# Groupe3_Hermant-Bohyn-Almasy-Ponjee.net
KiCad netlist of a schematic drawn in EAGLE
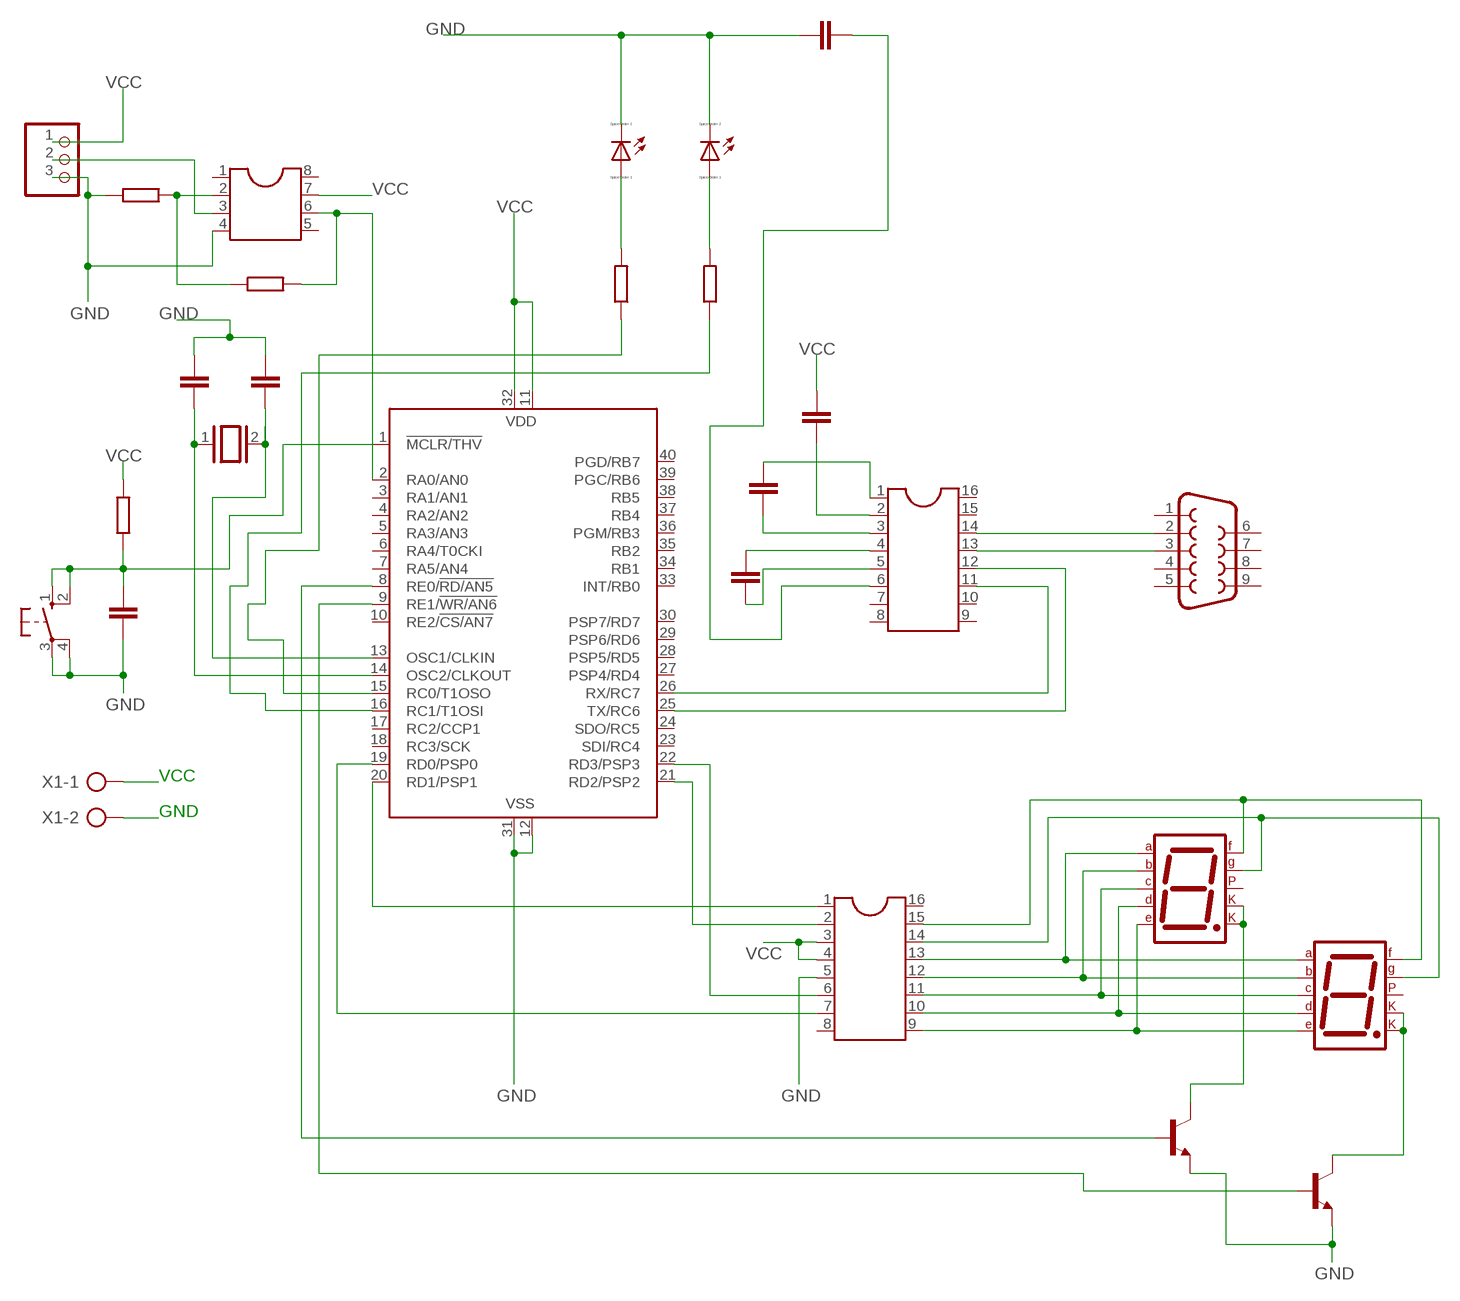
[diagram p0: schematic, sheet 1]

(export (version "E")
  (design (tool "Eeschema 10.0.6"))
  (components
    (comp (ref "4511")
      (value "DIL16")
      (footprint "eagle-import:DIL16")
      (libsource (lib "eagle-import") (part "DIL16"))
    )
    (comp (ref "AMPLIOP")
      (value "DIL8")
      (footprint "eagle-import:DIL08")
      (libsource (lib "eagle-import") (part "DIL8"))
    )
    (comp (ref "C1")
      (value "15pF")
      (footprint "eagle-import:C025-050X050")
      (libsource (lib "eagle-import") (part "C-EU025-050X050"))
    )
    (comp (ref "C2")
      (value "15pF")
      (footprint "eagle-import:C025-050X050")
      (libsource (lib "eagle-import") (part "C-EU025-050X050"))
    )
    (comp (ref "C3")
      (value "1uF")
      (footprint "eagle-import:C025-050X050")
      (libsource (lib "eagle-import") (part "C-EU025-050X050"))
    )
    (comp (ref "C4")
      (value "10uF")
      (footprint "eagle-import:C025-050X050")
      (libsource (lib "eagle-import") (part "C-EU025-050X050"))
    )
    (comp (ref "C5")
      (value "10uF")
      (footprint "eagle-import:C025-050X050")
      (libsource (lib "eagle-import") (part "C-EU025-050X050"))
    )
    (comp (ref "C7")
      (value "10uF")
      (footprint "eagle-import:C025-050X050")
      (libsource (lib "eagle-import") (part "C-EU025-050X050"))
    )
    (comp (ref "C61")
      (value "10uF")
      (footprint "eagle-import:C025-050X050")
      (libsource (lib "eagle-import") (part "C-EU025-050X050"))
    )
    (comp (ref "D1")
      (value "7SEG-CK")
      (footprint "eagle-import:7SEG-13")
      (libsource (lib "eagle-import") (part "7SEG-CK"))
    )
    (comp (ref "D2")
      (value "7SEG-CK")
      (footprint "eagle-import:7SEG-13")
      (libsource (lib "eagle-import") (part "7SEG-CK"))
    )
    (comp (ref "LED1")
      (value "LED_ELD260")
      (footprint "eagle-import:LED_LD260")
      (libsource (lib "eagle-import") (part "LED_ELD260"))
    )
    (comp (ref "LED2")
      (value "LED_ELD260")
      (footprint "eagle-import:LED_LD260")
      (libsource (lib "eagle-import") (part "LED_ELD260"))
    )
    (comp (ref "LM35")
      (value "PINHD-1X3")
      (footprint "eagle-import:1X03")
      (libsource (lib "eagle-import") (part "PINHD-1X3"))
    )
    (comp (ref "MAX232")
      (value "DIL16")
      (footprint "eagle-import:DIL16")
      (libsource (lib "eagle-import") (part "DIL16"))
    )
    (comp (ref "P1/COMPIM")
      (value "F09V")
      (footprint "eagle-import:F09V")
      (libsource (lib "eagle-import") (part "F09V"))
    )
    (comp (ref "Q1")
      (value "2N2222")
      (footprint "eagle-import:TO18")
      (libsource (lib "eagle-import") (part "2N2222"))
    )
    (comp (ref "Q2")
      (value "2N2222")
      (footprint "eagle-import:TO18")
      (libsource (lib "eagle-import") (part "2N2222"))
    )
    (comp (ref "R1")
      (value "10k")
      (footprint "eagle-import:0204_7")
      (libsource (lib "eagle-import") (part "R-EU_0204/7"))
    )
    (comp (ref "R2")
      (value "4k")
      (footprint "eagle-import:0204_7")
      (libsource (lib "eagle-import") (part "R-EU_0204/7"))
    )
    (comp (ref "R3")
      (value "1k")
      (footprint "eagle-import:0204_7")
      (libsource (lib "eagle-import") (part "R-EU_0204/7"))
    )
    (comp (ref "R4")
      (value "280")
      (footprint "eagle-import:0204_7")
      (libsource (lib "eagle-import") (part "R-EU_0204/7"))
    )
    (comp (ref "R5")
      (value "280")
      (footprint "eagle-import:0204_7")
      (libsource (lib "eagle-import") (part "R-EU_0204/7"))
    )
    (comp (ref "S1")
      (value "10-XX")
      (footprint "eagle-import:B3F-10XX")
      (fields (field (name "MPN") "B3F-1000"))
      (libsource (lib "eagle-import") (part "10-XX"))
    )
    (comp (ref "U1")
      (value "PIC16F877P")
      (footprint "eagle-import:DIL40")
      (fields (field (name "MF") "MICROCHIP") (field (name "MPN") "PIC16F877-04/P"))
      (libsource (lib "eagle-import") (part "PIC16F87P7"))
    )
    (comp (ref "X1")
      (value "AK300/2")
      (footprint "eagle-import:AK300_2")
      (libsource (lib "eagle-import") (part "AK300/2"))
    )
    (comp (ref "X11")
      (value "XTAL/S")
      (footprint "eagle-import:QS")
      (libsource (lib "eagle-import") (part "XTAL/S"))
    )
  )
  (nets
    (net (code "1") (name "/GND") (class "Default")
      (node (ref "4511") (pin "5") (pinfunction "5_5") (pintype "passive"))
      (node (ref "AMPLIOP") (pin "4") (pinfunction "4_4") (pintype "passive"))
      (node (ref "C1") (pin "1") (pinfunction "1_1") (pintype "passive"))
      (node (ref "C2") (pin "1") (pinfunction "1_1") (pintype "passive"))
      (node (ref "C3") (pin "1") (pinfunction "1_1") (pintype "passive"))
      (node (ref "C61") (pin "2") (pinfunction "2_2") (pintype "passive"))
      (node (ref "LED1") (pin "K") (pinfunction "C_K") (pintype "passive"))
      (node (ref "LED2") (pin "K") (pinfunction "C_K") (pintype "passive"))
      (node (ref "LM35") (pin "3") (pinfunction "3_3") (pintype "passive"))
      (node (ref "Q1") (pin "1") (pinfunction "E_1") (pintype "passive"))
      (node (ref "Q2") (pin "1") (pinfunction "E_1") (pintype "passive"))
      (node (ref "R2") (pin "1") (pinfunction "1_1") (pintype "passive"))
      (node (ref "S1") (pin "3") (pinfunction "P_3") (pintype "passive"))
      (node (ref "S1") (pin "4") (pinfunction "P1_4") (pintype "passive"))
      (node (ref "U1") (pin "12") (pinfunction "VSS_12") (pintype "power_in"))
      (node (ref "U1") (pin "31") (pinfunction "VSS_31") (pintype "power_in"))
      (node (ref "X1") (pin "2") (pinfunction "KL_2") (pintype "passive"))
    )
    (net (code "2") (name "/VCC") (class "Default")
      (node (ref "4511") (pin "3") (pinfunction "3_3") (pintype "passive"))
      (node (ref "4511") (pin "4") (pinfunction "4_4") (pintype "passive"))
      (node (ref "AMPLIOP") (pin "7") (pinfunction "7_7") (pintype "passive"))
      (node (ref "C7") (pin "2") (pinfunction "2_2") (pintype "passive"))
      (node (ref "LM35") (pin "1") (pinfunction "1_1") (pintype "passive"))
      (node (ref "R1") (pin "2") (pinfunction "2_2") (pintype "passive"))
      (node (ref "U1") (pin "11") (pinfunction "VDD_11") (pintype "power_in"))
      (node (ref "U1") (pin "32") (pinfunction "VDD_32") (pintype "power_in"))
      (node (ref "X1") (pin "1") (pinfunction "KL_1") (pintype "passive"))
    )
    (net (code "3") (name "Net-(AMPLIOP-Pad2)") (class "Default")
      (node (ref "AMPLIOP") (pin "2") (pinfunction "2_2") (pintype "passive"))
      (node (ref "R2") (pin "2") (pinfunction "2_2") (pintype "passive"))
      (node (ref "R3") (pin "1") (pinfunction "1_1") (pintype "passive"))
    )
    (net (code "4") (name "Net-(AMPLIOP-Pad3)") (class "Default")
      (node (ref "AMPLIOP") (pin "3") (pinfunction "3_3") (pintype "passive"))
      (node (ref "LM35") (pin "2") (pinfunction "2_2") (pintype "passive"))
    )
    (net (code "5") (name "Net-(C4-Pad1)") (class "Default")
      (node (ref "C4") (pin "1") (pinfunction "1_1") (pintype "passive"))
      (node (ref "MAX232") (pin "3") (pinfunction "3_3") (pintype "passive"))
    )
    (net (code "6") (name "Net-(C4-Pad2)") (class "Default")
      (node (ref "C4") (pin "2") (pinfunction "2_2") (pintype "passive"))
      (node (ref "MAX232") (pin "1") (pinfunction "1_1") (pintype "passive"))
    )
    (net (code "7") (name "Net-(C5-Pad1)") (class "Default")
      (node (ref "C5") (pin "1") (pinfunction "1_1") (pintype "passive"))
      (node (ref "MAX232") (pin "5") (pinfunction "5_5") (pintype "passive"))
    )
    (net (code "8") (name "Net-(C5-Pad2)") (class "Default")
      (node (ref "C5") (pin "2") (pinfunction "2_2") (pintype "passive"))
      (node (ref "MAX232") (pin "4") (pinfunction "4_4") (pintype "passive"))
    )
    (net (code "9") (name "Net-(C7-Pad1)") (class "Default")
      (node (ref "C7") (pin "1") (pinfunction "1_1") (pintype "passive"))
      (node (ref "MAX232") (pin "2") (pinfunction "2_2") (pintype "passive"))
    )
    (net (code "10") (name "Net-(C61-Pad1)") (class "Default")
      (node (ref "C61") (pin "1") (pinfunction "1_1") (pintype "passive"))
      (node (ref "MAX232") (pin "6") (pinfunction "6_6") (pintype "passive"))
    )
    (net (code "11") (name "Net-(D1-A)") (class "Default")
      (node (ref "4511") (pin "13") (pinfunction "13_13") (pintype "passive"))
      (node (ref "D1") (pin "7") (pinfunction "A_7") (pintype "passive"))
      (node (ref "D2") (pin "7") (pinfunction "A_7") (pintype "passive"))
    )
    (net (code "12") (name "Net-(D1-B)") (class "Default")
      (node (ref "4511") (pin "12") (pinfunction "12_12") (pintype "passive"))
      (node (ref "D1") (pin "6") (pinfunction "B_6") (pintype "passive"))
      (node (ref "D2") (pin "6") (pinfunction "B_6") (pintype "passive"))
    )
    (net (code "13") (name "Net-(D1-C)") (class "Default")
      (node (ref "4511") (pin "11") (pinfunction "11_11") (pintype "passive"))
      (node (ref "D1") (pin "4") (pinfunction "C_4") (pintype "passive"))
      (node (ref "D2") (pin "4") (pinfunction "C_4") (pintype "passive"))
    )
    (net (code "14") (name "Net-(D1-CK1)") (class "Default")
      (node (ref "D1") (pin "3") (pinfunction "CK1_3") (pintype "passive"))
      (node (ref "D1") (pin "8") (pinfunction "CK2_8") (pintype "passive"))
      (node (ref "Q1") (pin "3") (pinfunction "C_3") (pintype "passive"))
    )
    (net (code "15") (name "Net-(D1-D)") (class "Default")
      (node (ref "4511") (pin "10") (pinfunction "10_10") (pintype "passive"))
      (node (ref "D1") (pin "2") (pinfunction "D_2") (pintype "passive"))
      (node (ref "D2") (pin "2") (pinfunction "D_2") (pintype "passive"))
    )
    (net (code "16") (name "Net-(D1-E)") (class "Default")
      (node (ref "4511") (pin "9") (pinfunction "9_9") (pintype "passive"))
      (node (ref "D1") (pin "1") (pinfunction "E_1") (pintype "passive"))
      (node (ref "D2") (pin "1") (pinfunction "E_1") (pintype "passive"))
    )
    (net (code "17") (name "Net-(D1-F)") (class "Default")
      (node (ref "4511") (pin "15") (pinfunction "15_15") (pintype "passive"))
      (node (ref "D1") (pin "9") (pinfunction "F_9") (pintype "passive"))
      (node (ref "D2") (pin "9") (pinfunction "F_9") (pintype "passive"))
    )
    (net (code "18") (name "Net-(D1-G)") (class "Default")
      (node (ref "4511") (pin "14") (pinfunction "14_14") (pintype "passive"))
      (node (ref "D1") (pin "10") (pinfunction "G_10") (pintype "passive"))
      (node (ref "D2") (pin "10") (pinfunction "G_10") (pintype "passive"))
    )
    (net (code "19") (name "Net-(D2-CK1)") (class "Default")
      (node (ref "D2") (pin "3") (pinfunction "CK1_3") (pintype "passive"))
      (node (ref "D2") (pin "8") (pinfunction "CK2_8") (pintype "passive"))
      (node (ref "Q2") (pin "3") (pinfunction "C_3") (pintype "passive"))
    )
    (net (code "20") (name "Net-(LED1-PadA)") (class "Default")
      (node (ref "LED1") (pin "A") (pinfunction "A_A") (pintype "passive"))
      (node (ref "R4") (pin "2") (pinfunction "2_2") (pintype "passive"))
    )
    (net (code "21") (name "Net-(LED2-PadA)") (class "Default")
      (node (ref "LED2") (pin "A") (pinfunction "A_A") (pintype "passive"))
      (node (ref "R5") (pin "2") (pinfunction "2_2") (pintype "passive"))
    )
    (net (code "22") (name "Net-(MAX232-Pad13)") (class "Default")
      (node (ref "MAX232") (pin "13") (pinfunction "13_13") (pintype "passive"))
      (node (ref "P1/COMPIM") (pin "3") (pinfunction "3_3") (pintype "passive"))
    )
    (net (code "23") (name "Net-(MAX232-Pad14)") (class "Default")
      (node (ref "MAX232") (pin "14") (pinfunction "14_14") (pintype "passive"))
      (node (ref "P1/COMPIM") (pin "2") (pinfunction "2_2") (pintype "passive"))
    )
    (net (code "24") (name "Net-(Q1-B)") (class "Default")
      (node (ref "Q1") (pin "2") (pinfunction "B_2") (pintype "passive"))
      (node (ref "U1") (pin "8") (pinfunction "RE0/~{RD/AN5}_8") (pintype "bidirectional"))
    )
    (net (code "25") (name "Net-(Q2-B)") (class "Default")
      (node (ref "Q2") (pin "2") (pinfunction "B_2") (pintype "passive"))
      (node (ref "U1") (pin "9") (pinfunction "RE1/~{WR/AN6}_9") (pintype "bidirectional"))
    )
    (net (code "26") (name "Net-(S1-S)") (class "Default")
      (node (ref "C3") (pin "2") (pinfunction "2_2") (pintype "passive"))
      (node (ref "R1") (pin "1") (pinfunction "1_1") (pintype "passive"))
      (node (ref "S1") (pin "1") (pinfunction "S_1") (pintype "passive"))
      (node (ref "S1") (pin "2") (pinfunction "S1_2") (pintype "passive"))
      (node (ref "U1") (pin "1") (pinfunction "~{MCLR/THV}_1") (pintype "input"))
    )
    (net (code "27") (name "Net-(U1-OSC1{slash}CLKIN)") (class "Default")
      (node (ref "C1") (pin "2") (pinfunction "2_2") (pintype "passive"))
      (node (ref "U1") (pin "13") (pinfunction "OSC1/CLKIN_13") (pintype "input"))
      (node (ref "X11") (pin "2") (pinfunction "2_2") (pintype "passive"))
    )
    (net (code "28") (name "Net-(U1-OSC2{slash}CLKOUT)") (class "Default")
      (node (ref "C2") (pin "2") (pinfunction "2_2") (pintype "passive"))
      (node (ref "U1") (pin "14") (pinfunction "OSC2/CLKOUT_14") (pintype "output"))
      (node (ref "X11") (pin "1") (pinfunction "1_1") (pintype "passive"))
    )
    (net (code "29") (name "Net-(U1-RA0{slash}AN0)") (class "Default")
      (node (ref "AMPLIOP") (pin "6") (pinfunction "6_6") (pintype "passive"))
      (node (ref "R3") (pin "2") (pinfunction "2_2") (pintype "passive"))
      (node (ref "U1") (pin "2") (pinfunction "RA0/AN0_2") (pintype "bidirectional"))
    )
    (net (code "30") (name "Net-(U1-RC0{slash}T1OSO)") (class "Default")
      (node (ref "R4") (pin "1") (pinfunction "1_1") (pintype "passive"))
      (node (ref "U1") (pin "15") (pinfunction "RC0/T1OSO_15") (pintype "bidirectional"))
    )
    (net (code "31") (name "Net-(U1-RC1{slash}T1OSI)") (class "Default")
      (node (ref "R5") (pin "1") (pinfunction "1_1") (pintype "passive"))
      (node (ref "U1") (pin "16") (pinfunction "RC1/T1OSI_16") (pintype "bidirectional"))
    )
    (net (code "32") (name "Net-(U1-RD0{slash}PSP0)") (class "Default")
      (node (ref "4511") (pin "7") (pinfunction "7_7") (pintype "passive"))
      (node (ref "U1") (pin "19") (pinfunction "RD0/PSP0_19") (pintype "bidirectional"))
    )
    (net (code "33") (name "Net-(U1-RD1{slash}PSP1)") (class "Default")
      (node (ref "4511") (pin "1") (pinfunction "1_1") (pintype "passive"))
      (node (ref "U1") (pin "20") (pinfunction "RD1/PSP1_20") (pintype "bidirectional"))
    )
    (net (code "34") (name "Net-(U1-RD2{slash}PSP2)") (class "Default")
      (node (ref "4511") (pin "2") (pinfunction "2_2") (pintype "passive"))
      (node (ref "U1") (pin "21") (pinfunction "RD2/PSP2_21") (pintype "bidirectional"))
    )
    (net (code "35") (name "Net-(U1-RD3{slash}PSP3)") (class "Default")
      (node (ref "4511") (pin "6") (pinfunction "6_6") (pintype "passive"))
      (node (ref "U1") (pin "22") (pinfunction "RD3/PSP3_22") (pintype "bidirectional"))
    )
    (net (code "36") (name "Net-(U1-RX{slash}RC7)") (class "Default")
      (node (ref "MAX232") (pin "11") (pinfunction "11_11") (pintype "passive"))
      (node (ref "U1") (pin "26") (pinfunction "RX/RC7_26") (pintype "bidirectional"))
    )
    (net (code "37") (name "Net-(U1-TX{slash}RC6)") (class "Default")
      (node (ref "MAX232") (pin "12") (pinfunction "12_12") (pintype "passive"))
      (node (ref "U1") (pin "25") (pinfunction "TX/RC6_25") (pintype "bidirectional"))
    )
    (net (code "38") (name "unconnected-(4511-Pad8)") (class "Default")
      (node (ref "4511") (pin "8") (pinfunction "8_8") (pintype "passive"))
    )
    (net (code "39") (name "unconnected-(4511-Pad16)") (class "Default")
      (node (ref "4511") (pin "16") (pinfunction "16_16") (pintype "passive"))
    )
    (net (code "40") (name "unconnected-(AMPLIOP-Pad1)") (class "Default")
      (node (ref "AMPLIOP") (pin "1") (pinfunction "1_1") (pintype "passive"))
    )
    (net (code "41") (name "unconnected-(AMPLIOP-Pad5)") (class "Default")
      (node (ref "AMPLIOP") (pin "5") (pinfunction "5_5") (pintype "passive"))
    )
    (net (code "42") (name "unconnected-(AMPLIOP-Pad8)") (class "Default")
      (node (ref "AMPLIOP") (pin "8") (pinfunction "8_8") (pintype "passive"))
    )
    (net (code "43") (name "unconnected-(D1-DP-Pad5)") (class "Default")
      (node (ref "D1") (pin "5") (pinfunction "DP_5") (pintype "passive"))
    )
    (net (code "44") (name "unconnected-(D2-DP-Pad5)") (class "Default")
      (node (ref "D2") (pin "5") (pinfunction "DP_5") (pintype "passive"))
    )
    (net (code "45") (name "unconnected-(MAX232-Pad7)") (class "Default")
      (node (ref "MAX232") (pin "7") (pinfunction "7_7") (pintype "passive"))
    )
    (net (code "46") (name "unconnected-(MAX232-Pad8)") (class "Default")
      (node (ref "MAX232") (pin "8") (pinfunction "8_8") (pintype "passive"))
    )
    (net (code "47") (name "unconnected-(MAX232-Pad9)") (class "Default")
      (node (ref "MAX232") (pin "9") (pinfunction "9_9") (pintype "passive"))
    )
    (net (code "48") (name "unconnected-(MAX232-Pad10)") (class "Default")
      (node (ref "MAX232") (pin "10") (pinfunction "10_10") (pintype "passive"))
    )
    (net (code "49") (name "unconnected-(MAX232-Pad15)") (class "Default")
      (node (ref "MAX232") (pin "15") (pinfunction "15_15") (pintype "passive"))
    )
    (net (code "50") (name "unconnected-(MAX232-Pad16)") (class "Default")
      (node (ref "MAX232") (pin "16") (pinfunction "16_16") (pintype "passive"))
    )
    (net (code "51") (name "unconnected-(P1/COMPIM-Pad1)") (class "Default")
      (node (ref "P1/COMPIM") (pin "1") (pinfunction "1_1") (pintype "passive"))
    )
    (net (code "52") (name "unconnected-(P1/COMPIM-Pad4)") (class "Default")
      (node (ref "P1/COMPIM") (pin "4") (pinfunction "4_4") (pintype "passive"))
    )
    (net (code "53") (name "unconnected-(P1/COMPIM-Pad5)") (class "Default")
      (node (ref "P1/COMPIM") (pin "5") (pinfunction "5_5") (pintype "passive"))
    )
    (net (code "54") (name "unconnected-(P1/COMPIM-Pad6)") (class "Default")
      (node (ref "P1/COMPIM") (pin "6") (pinfunction "6_6") (pintype "passive"))
    )
    (net (code "55") (name "unconnected-(P1/COMPIM-Pad7)") (class "Default")
      (node (ref "P1/COMPIM") (pin "7") (pinfunction "7_7") (pintype "passive"))
    )
    (net (code "56") (name "unconnected-(P1/COMPIM-Pad8)") (class "Default")
      (node (ref "P1/COMPIM") (pin "8") (pinfunction "8_8") (pintype "passive"))
    )
    (net (code "57") (name "unconnected-(P1/COMPIM-Pad9)") (class "Default")
      (node (ref "P1/COMPIM") (pin "9") (pinfunction "9_9") (pintype "passive"))
    )
    (net (code "58") (name "unconnected-(U1-INT{slash}RB0-Pad33)") (class "Default")
      (node (ref "U1") (pin "33") (pinfunction "INT/RB0_33") (pintype "bidirectional"))
    )
    (net (code "59") (name "unconnected-(U1-PGC{slash}RB6-Pad39)") (class "Default")
      (node (ref "U1") (pin "39") (pinfunction "PGC/RB6_39") (pintype "bidirectional"))
    )
    (net (code "60") (name "unconnected-(U1-PGD{slash}RB7-Pad40)") (class "Default")
      (node (ref "U1") (pin "40") (pinfunction "PGD/RB7_40") (pintype "bidirectional"))
    )
    (net (code "61") (name "unconnected-(U1-PGM{slash}RB3-Pad36)") (class "Default")
      (node (ref "U1") (pin "36") (pinfunction "PGM/RB3_36") (pintype "bidirectional"))
    )
    (net (code "62") (name "unconnected-(U1-PSP4{slash}RD4-Pad27)") (class "Default")
      (node (ref "U1") (pin "27") (pinfunction "PSP4/RD4_27") (pintype "bidirectional"))
    )
    (net (code "63") (name "unconnected-(U1-PSP5{slash}RD5-Pad28)") (class "Default")
      (node (ref "U1") (pin "28") (pinfunction "PSP5/RD5_28") (pintype "bidirectional"))
    )
    (net (code "64") (name "unconnected-(U1-PSP6{slash}RD6-Pad29)") (class "Default")
      (node (ref "U1") (pin "29") (pinfunction "PSP6/RD6_29") (pintype "bidirectional"))
    )
    (net (code "65") (name "unconnected-(U1-PSP7{slash}RD7-Pad30)") (class "Default")
      (node (ref "U1") (pin "30") (pinfunction "PSP7/RD7_30") (pintype "bidirectional"))
    )
    (net (code "66") (name "unconnected-(U1-RA1{slash}AN1-Pad3)") (class "Default")
      (node (ref "U1") (pin "3") (pinfunction "RA1/AN1_3") (pintype "bidirectional"))
    )
    (net (code "67") (name "unconnected-(U1-RA2{slash}AN2-Pad4)") (class "Default")
      (node (ref "U1") (pin "4") (pinfunction "RA2/AN2_4") (pintype "bidirectional"))
    )
    (net (code "68") (name "unconnected-(U1-RA3{slash}AN3-Pad5)") (class "Default")
      (node (ref "U1") (pin "5") (pinfunction "RA3/AN3_5") (pintype "bidirectional"))
    )
    (net (code "69") (name "unconnected-(U1-RA4{slash}T0CKI-Pad6)") (class "Default")
      (node (ref "U1") (pin "6") (pinfunction "RA4/T0CKI_6") (pintype "bidirectional"))
    )
    (net (code "70") (name "unconnected-(U1-RA5{slash}AN4-Pad7)") (class "Default")
      (node (ref "U1") (pin "7") (pinfunction "RA5/AN4_7") (pintype "bidirectional"))
    )
    (net (code "71") (name "unconnected-(U1-RB1-Pad34)") (class "Default")
      (node (ref "U1") (pin "34") (pinfunction "RB1_34") (pintype "bidirectional"))
    )
    (net (code "72") (name "unconnected-(U1-RB2-Pad35)") (class "Default")
      (node (ref "U1") (pin "35") (pinfunction "RB2_35") (pintype "bidirectional"))
    )
    (net (code "73") (name "unconnected-(U1-RB4-Pad37)") (class "Default")
      (node (ref "U1") (pin "37") (pinfunction "RB4_37") (pintype "bidirectional"))
    )
    (net (code "74") (name "unconnected-(U1-RB5-Pad38)") (class "Default")
      (node (ref "U1") (pin "38") (pinfunction "RB5_38") (pintype "bidirectional"))
    )
    (net (code "75") (name "unconnected-(U1-RC2{slash}CCP1-Pad17)") (class "Default")
      (node (ref "U1") (pin "17") (pinfunction "RC2/CCP1_17") (pintype "bidirectional"))
    )
    (net (code "76") (name "unconnected-(U1-RC3{slash}SCK-Pad18)") (class "Default")
      (node (ref "U1") (pin "18") (pinfunction "RC3/SCK_18") (pintype "bidirectional"))
    )
    (net (code "77") (name "unconnected-(U1-RE2{slash}~{CS{slash}AN7}-Pad10)") (class "Default")
      (node (ref "U1") (pin "10") (pinfunction "RE2/~{CS/AN7}_10") (pintype "bidirectional"))
    )
    (net (code "78") (name "unconnected-(U1-SDI{slash}RC4-Pad23)") (class "Default")
      (node (ref "U1") (pin "23") (pinfunction "SDI/RC4_23") (pintype "bidirectional"))
    )
    (net (code "79") (name "unconnected-(U1-SDO{slash}RC5-Pad24)") (class "Default")
      (node (ref "U1") (pin "24") (pinfunction "SDO/RC5_24") (pintype "bidirectional"))
    )
  )
)
